# Buck_converter.net
KiCad netlist of a schematic drawn in Altium Designer
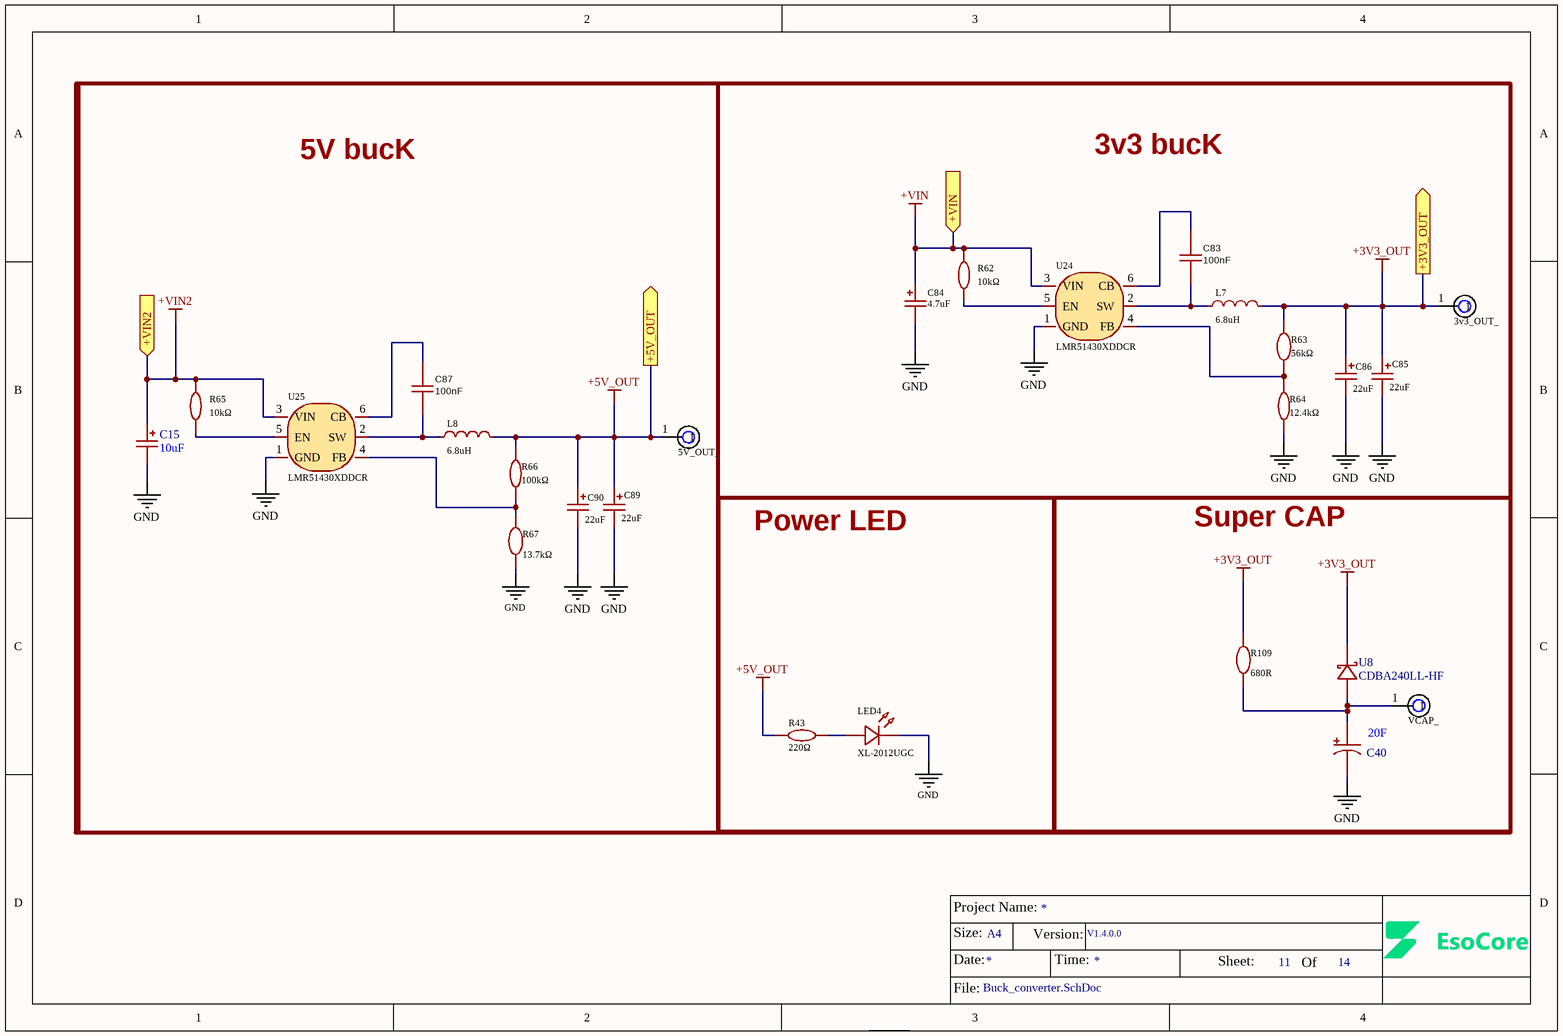
[diagram p0: Buck_converter.SchDoc]

(export (version "E")
  (design (tool "Eeschema 10.0.6"))
  (components
    (comp (ref "3v3_OUT_") (value "TP") (footprint "TP") (libsource (lib "Schlib1") (part "TP")))
    (comp (ref "5V_OUT_") (value "TP") (footprint "TP") (libsource (lib "Schlib1") (part "TP")))
    (comp (ref "C15")
      (value "10uF")
      (footprint "CASE-C_6032")
      (fields
        (field (name "MANUFACTURER") "Kyocera AVX")
        (field (name "MANUFACTURER PART") "TAJC106K035RNJ")
        (field (name "TOLERANCE") "±10%")
      )
      (libsource (lib "altium-import") (part "root_1_TAJC106K035RNJ_"))
    )
    (comp (ref "C40")
      (value "20F")
      (footprint "CAP-TH_BD8.0-P3.50-D0.6-FD")
      (fields
        (field (name "MANUFACTURER") "Ymin(永铭)")
        (field (name "MANUFACTURER PART") "SLA3R8L2060813")
        (field (name "TOLERANCE") "-10%~+30%")
      )
      (libsource (lib "altium-import") (part "root_0_SLA3R8L2060813_"))
    )
    (comp (ref "C83")
      (value "100nF")
      (footprint "C_0805")
      (fields
        (field (name "MANUFACTURER PART") "CC0805KRX7R9BB104")
        (field (name "MANUFACTURER") "YAGEO(国巨)")
      )
      (libsource (lib "altium-import") (part "root_1_100nF_"))
    )
    (comp (ref "C84")
      (value "4.7uF")
      (footprint "CAP-SMD_L6.0-W3.2-R-RD")
      (fields
        (field (name "MANUFACTURER") "Kyocera AVX")
        (field (name "MANUFACTURER PART") "TAJC475K035RNJ")
        (field (name "TOLERANCE") "±10%")
      )
      (libsource (lib "altium-import") (part "root_1_mirrored_TAJC475K035RNJ_"))
    )
    (comp (ref "C85")
      (value "22uF")
      (footprint "CASE-A_3216")
      (fields
        (field (name "MANUFACTURER") "Kyocera AVX")
        (field (name "MANUFACTURER PART") "TAJA226K010RNJ")
        (field (name "TOLERANCE") "±10%")
      )
      (libsource (lib "altium-import") (part "root_1_TAJA226K010RNJ_"))
    )
    (comp (ref "C86")
      (value "22uF")
      (footprint "CASE-A_3216")
      (fields
        (field (name "MANUFACTURER") "Kyocera AVX")
        (field (name "MANUFACTURER PART") "TAJA226K010RNJ")
        (field (name "TOLERANCE") "±10%")
      )
      (libsource (lib "altium-import") (part "root_1_TAJA226K010RNJ_"))
    )
    (comp (ref "C87")
      (value "100nF")
      (footprint "C_0805")
      (fields
        (field (name "MANUFACTURER PART") "CC0805KRX7R9BB104")
        (field (name "MANUFACTURER") "YAGEO(国巨)")
      )
      (libsource (lib "altium-import") (part "root_1_100nF_"))
    )
    (comp (ref "C89")
      (value "22uF")
      (footprint "CASE-A_3216")
      (fields
        (field (name "MANUFACTURER") "Kyocera AVX")
        (field (name "MANUFACTURER PART") "TAJA226K010RNJ")
        (field (name "TOLERANCE") "±10%")
      )
      (libsource (lib "altium-import") (part "root_1_TAJA226K010RNJ_"))
    )
    (comp (ref "C90")
      (value "22uF")
      (footprint "CASE-A_3216")
      (fields
        (field (name "MANUFACTURER") "Kyocera AVX")
        (field (name "MANUFACTURER PART") "TAJA226K010RNJ")
        (field (name "TOLERANCE") "±10%")
      )
      (libsource (lib "altium-import") (part "root_1_TAJA226K010RNJ_"))
    )
    (comp (ref "L7")
      (value "6.8uH")
      (footprint "IND-SMD_L5.4-W5.2_SLO0530H6R8MTT")
      (fields
        (field (name "MANUFACTURER") "Sunltech(顺磁)")
        (field (name "MANUFACTURER PART") "SLO0530H6R8MTT")
        (field (name "TOLERANCE") "±20%")
      )
      (libsource (lib "altium-import") (part "root_0_SLO0530H6R8MTT_"))
    )
    (comp (ref "L8")
      (value "6.8uH")
      (footprint "IND-SMD_L5.4-W5.2_SLO0530H6R8MTT")
      (fields
        (field (name "MANUFACTURER") "Sunltech(顺磁)")
        (field (name "MANUFACTURER PART") "SLO0530H6R8MTT")
        (field (name "TOLERANCE") "±20%")
      )
      (libsource (lib "altium-import") (part "root_0_SLO0530H6R8MTT_"))
    )
    (comp (ref "LED4")
      (value "XL-2012UGC")
      (footprint "LED0805-RD_GREEN")
      (fields (field (name "MANUFACTURER") "XINGLIGHT(成兴光)"))
      (libsource (lib "altium-import") (part "root_0_mirrored_XL-2012UGC_"))
    )
    (comp (ref "R43")
      (value "220Ω")
      (footprint "R_0603")
      (fields
        (field (name "MANUFACTURER") "YAGEO(国巨)")
        (field (name "MANUFACTURER PART") "RC0603FR-07220RL")
        (field (name "TOLERANCE") "±1%")
      )
      (libsource (lib "altium-import") (part "root_0_mirrored_RC0603FR-07220RL_"))
    )
    (comp (ref "R62")
      (value "10kΩ")
      (footprint "R_0603")
      (fields
        (field (name "MANUFACTURER") "YAGEO(国巨)")
        (field (name "MANUFACTURER PART") "RC0603FR-0710KL")
        (field (name "TOLERANCE") "±1%")
      )
      (libsource (lib "altium-import") (part "root_1_RC0603FR-0710KL_"))
    )
    (comp (ref "R63")
      (value "56kΩ")
      (footprint "R_0805")
      (fields
        (field (name "MANUFACTURER") "YAGEO(国巨)")
        (field (name "MANUFACTURER PART") "RT0805BRC0756KL")
        (field (name "TOLERANCE") "±0.1%")
      )
      (libsource (lib "altium-import") (part "root_1_RT0805BRC0756KL_"))
    )
    (comp (ref "R64")
      (value "12.4kΩ")
      (footprint "R_0805")
      (fields
        (field (name "MANUFACTURER") "YAGEO(国巨)")
        (field (name "MANUFACTURER PART") "RC0805FR-0712K4L")
        (field (name "TOLERANCE") "±1%")
      )
      (libsource (lib "altium-import") (part "root_1_RC0805FR-0712K4L_"))
    )
    (comp (ref "R65")
      (value "10kΩ")
      (footprint "R_0603")
      (fields
        (field (name "MANUFACTURER") "YAGEO(国巨)")
        (field (name "MANUFACTURER PART") "RC0603FR-0710KL")
        (field (name "TOLERANCE") "±1%")
      )
      (libsource (lib "altium-import") (part "root_1_RC0603FR-0710KL_"))
    )
    (comp (ref "R66")
      (value "100kΩ")
      (footprint "R_0805")
      (fields
        (field (name "MANUFACTURER") "YAGEO(国巨)")
        (field (name "MANUFACTURER PART") "RC0805FR-07100KL")
        (field (name "TOLERANCE") "±1%")
      )
      (libsource (lib "altium-import") (part "root_1_RC0805FR-07100KL_"))
    )
    (comp (ref "R67")
      (value "13.7kΩ")
      (footprint "R_0805")
      (fields
        (field (name "MANUFACTURER") "YAGEO(国巨)")
        (field (name "MANUFACTURER PART") "RT0805BRD0713K7L")
        (field (name "TOLERANCE") "±0.1%")
      )
      (libsource (lib "altium-import") (part "root_1_RT0805BRD0713K7L_"))
    )
    (comp (ref "R109")
      (value "680R")
      (footprint "R_0805")
      (fields
        (field (name "MANUFACTURER") "YAGEO(国巨)")
        (field (name "MANUFACTURER PART") "RT0805BRD0713K7L")
        (field (name "TOLERANCE") "±0.1%")
      )
      (libsource (lib "altium-import") (part "root_1_RT0805BRD0713K7L_"))
    )
    (comp (ref "U8")
      (value "CDBA240LL-HF")
      (footprint "SMA_L4.4-W2.5-LS5.2-R-RD")
      (fields (field (name "MANUFACTURER") "Comchip(典琦)"))
      (libsource (lib "altium-import") (part "root_3_CDBA240LL-HF_"))
    )
    (comp (ref "U24")
      (value "LMR51430XDDCR")
      (footprint "SOT-23-6_L2.9-W1.6-P0.95-LS2.8-BR")
      (fields (field (name "MANUFACTURER") "TI(德州仪器)"))
      (libsource (lib "EsoCore_Edge_Board_V1-0.0.0") (part "LMR51430XDDCR"))
    )
    (comp (ref "U25")
      (value "LMR51430XDDCR")
      (footprint "SOT-23-6_L2.9-W1.6-P0.95-LS2.8-BR")
      (fields (field (name "MANUFACTURER") "TI(德州仪器)"))
      (libsource (lib "EsoCore_Edge_Board_V1-0.0.0") (part "LMR51430XDDCR"))
    )
    (comp (ref "VCAP_") (value "TP") (footprint "TP") (libsource (lib "Schlib1") (part "TP")))
  )
  (nets
    (net (code "1") (name "+3V3_OUT") (class "Default")
      (node (ref "3v3_OUT_") (pin "1") (pinfunction "1_1") (pintype "passive"))
      (node (ref "C85") (pin "1") (pinfunction "1_1") (pintype "passive"))
      (node (ref "C86") (pin "1") (pinfunction "1_1") (pintype "passive"))
      (node (ref "L7") (pin "2") (pinfunction "2_2") (pintype "passive"))
      (node (ref "R109") (pin "2") (pinfunction "2_2") (pintype "passive"))
      (node (ref "R63") (pin "2") (pinfunction "2_2") (pintype "passive"))
      (node (ref "U8") (pin "2") (pinfunction "K_2") (pintype "passive"))
    )
    (net (code "2") (name "+5V_OUT") (class "Default")
      (node (ref "5V_OUT_") (pin "1") (pinfunction "1_1") (pintype "passive"))
      (node (ref "C89") (pin "1") (pinfunction "1_1") (pintype "passive"))
      (node (ref "C90") (pin "1") (pinfunction "1_1") (pintype "passive"))
      (node (ref "L8") (pin "2") (pinfunction "2_2") (pintype "passive"))
      (node (ref "R43") (pin "2") (pinfunction "2_2") (pintype "passive"))
      (node (ref "R66") (pin "2") (pinfunction "2_2") (pintype "passive"))
    )
    (net (code "3") (name "+VIN") (class "Default")
      (node (ref "C84") (pin "1") (pinfunction "1_1") (pintype "passive"))
      (node (ref "R62") (pin "2") (pinfunction "2_2") (pintype "passive"))
      (node (ref "U24") (pin "3") (pinfunction "VIN_3") (pintype "passive"))
    )
    (net (code "4") (name "+VIN2") (class "Default")
      (node (ref "C15") (pin "1") (pinfunction "1_1") (pintype "passive"))
      (node (ref "R65") (pin "2") (pinfunction "2_2") (pintype "passive"))
      (node (ref "U25") (pin "3") (pinfunction "VIN_3") (pintype "passive"))
    )
    (net (code "5") (name "GND") (class "Default")
      (node (ref "C15") (pin "2") (pinfunction "2_2") (pintype "passive"))
      (node (ref "C40") (pin "2") (pinfunction "2_2") (pintype "passive"))
      (node (ref "C84") (pin "2") (pinfunction "2_2") (pintype "passive"))
      (node (ref "C85") (pin "2") (pinfunction "2_2") (pintype "passive"))
      (node (ref "C86") (pin "2") (pinfunction "2_2") (pintype "passive"))
      (node (ref "C89") (pin "2") (pinfunction "2_2") (pintype "passive"))
      (node (ref "C90") (pin "2") (pinfunction "2_2") (pintype "passive"))
      (node (ref "LED4") (pin "1") (pinfunction "K_1") (pintype "passive"))
      (node (ref "R64") (pin "1") (pinfunction "1_1") (pintype "passive"))
      (node (ref "R67") (pin "1") (pinfunction "1_1") (pintype "passive"))
      (node (ref "U24") (pin "1") (pinfunction "GND_1") (pintype "passive"))
      (node (ref "U25") (pin "1") (pinfunction "GND_1") (pintype "passive"))
    )
    (net (code "6") (name "Net-(LED4-A)") (class "Default")
      (node (ref "LED4") (pin "2") (pinfunction "A_2") (pintype "passive"))
      (node (ref "R43") (pin "1") (pinfunction "1_1") (pintype "passive"))
    )
    (net (code "7") (name "Net-(U8-A)") (class "Default")
      (node (ref "C40") (pin "1") (pinfunction "1_1") (pintype "passive"))
      (node (ref "R109") (pin "1") (pinfunction "1_1") (pintype "passive"))
      (node (ref "U8") (pin "1") (pinfunction "A_1") (pintype "passive"))
      (node (ref "VCAP_") (pin "1") (pinfunction "1_1") (pintype "passive"))
    )
    (net (code "8") (name "Net-(U24-CB)") (class "Default")
      (node (ref "C83") (pin "2") (pinfunction "2_2") (pintype "passive"))
      (node (ref "U24") (pin "6") (pinfunction "CB_6") (pintype "passive"))
    )
    (net (code "9") (name "Net-(U24-EN)") (class "Default")
      (node (ref "R62") (pin "1") (pinfunction "1_1") (pintype "passive"))
      (node (ref "U24") (pin "5") (pinfunction "EN_5") (pintype "passive"))
    )
    (net (code "10") (name "Net-(U24-FB)") (class "Default")
      (node (ref "R63") (pin "1") (pinfunction "1_1") (pintype "passive"))
      (node (ref "R64") (pin "2") (pinfunction "2_2") (pintype "passive"))
      (node (ref "U24") (pin "4") (pinfunction "FB_4") (pintype "passive"))
    )
    (net (code "11") (name "Net-(U24-SW)") (class "Default")
      (node (ref "C83") (pin "1") (pinfunction "1_1") (pintype "passive"))
      (node (ref "L7") (pin "1") (pinfunction "1_1") (pintype "passive"))
      (node (ref "U24") (pin "2") (pinfunction "SW_2") (pintype "passive"))
    )
    (net (code "12") (name "Net-(U25-CB)") (class "Default")
      (node (ref "C87") (pin "2") (pinfunction "2_2") (pintype "passive"))
      (node (ref "U25") (pin "6") (pinfunction "CB_6") (pintype "passive"))
    )
    (net (code "13") (name "Net-(U25-EN)") (class "Default")
      (node (ref "R65") (pin "1") (pinfunction "1_1") (pintype "passive"))
      (node (ref "U25") (pin "5") (pinfunction "EN_5") (pintype "passive"))
    )
    (net (code "14") (name "Net-(U25-FB)") (class "Default")
      (node (ref "R66") (pin "1") (pinfunction "1_1") (pintype "passive"))
      (node (ref "R67") (pin "2") (pinfunction "2_2") (pintype "passive"))
      (node (ref "U25") (pin "4") (pinfunction "FB_4") (pintype "passive"))
    )
    (net (code "15") (name "Net-(U25-SW)") (class "Default")
      (node (ref "C87") (pin "1") (pinfunction "1_1") (pintype "passive"))
      (node (ref "L8") (pin "1") (pinfunction "1_1") (pintype "passive"))
      (node (ref "U25") (pin "2") (pinfunction "SW_2") (pintype "passive"))
    )
  )
)
